# PWR_DC_IN.net
KiCad netlist of a schematic drawn in Altium Designer
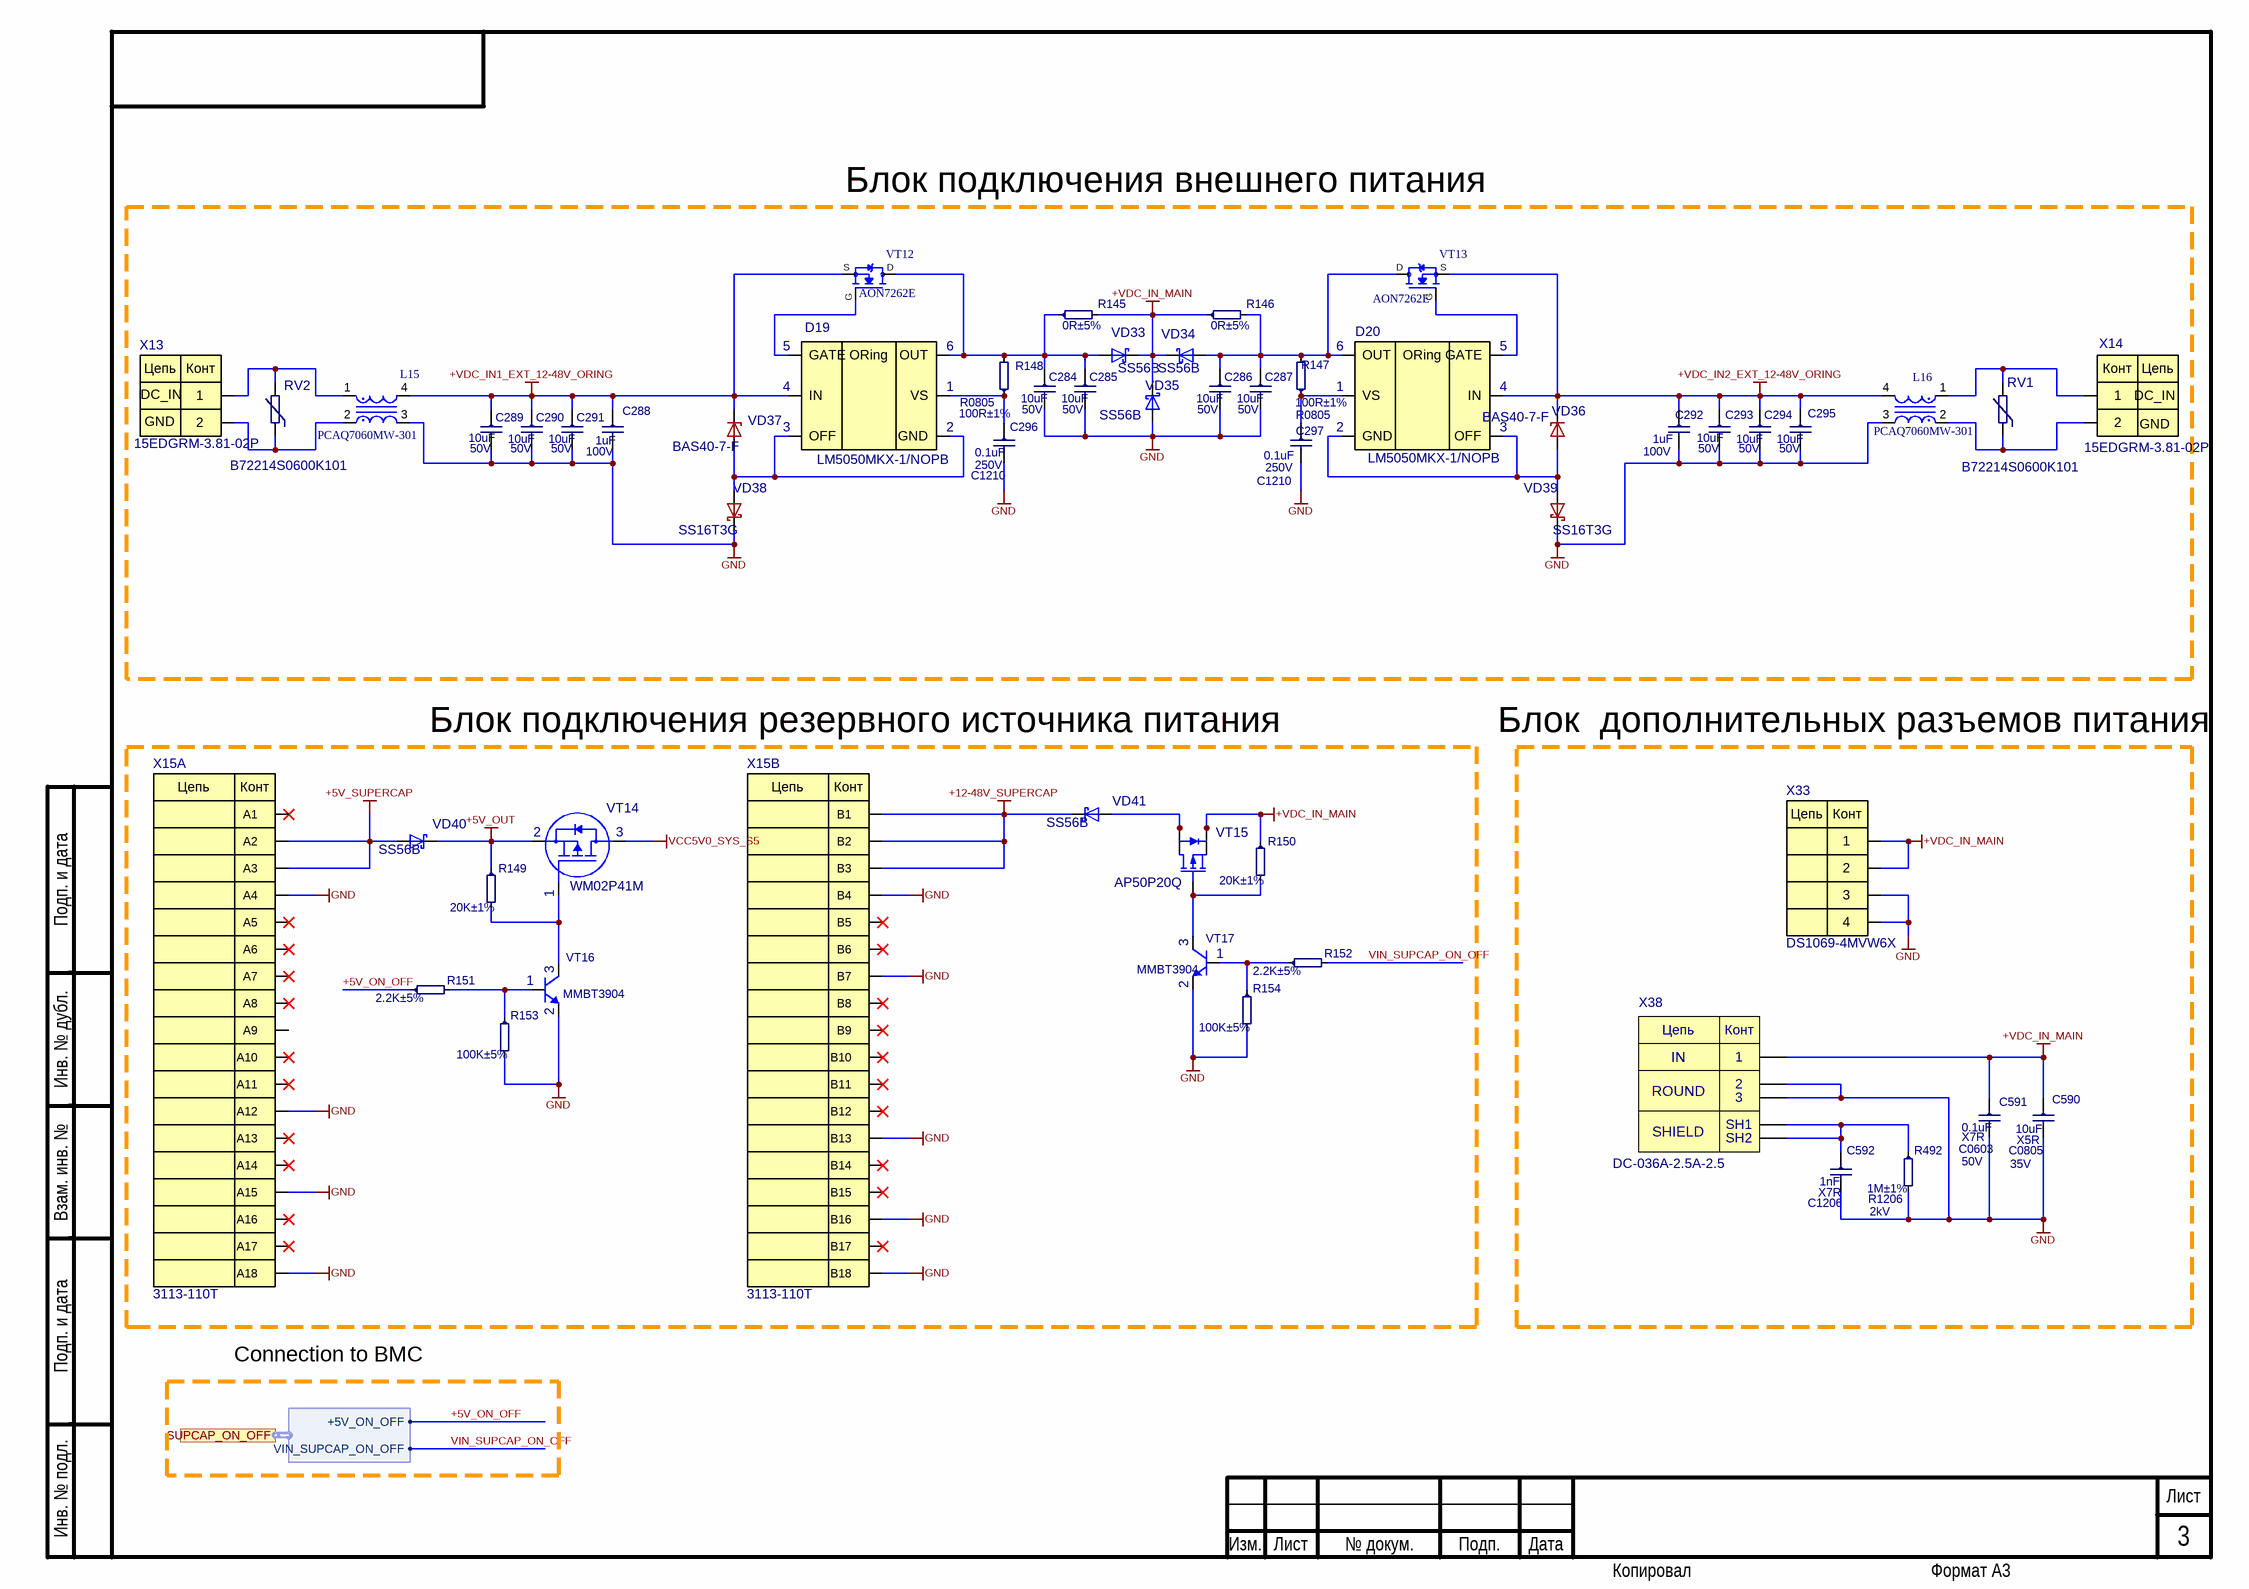
[diagram p0: PWR_DC_IN.SchDoc]

(export (version "E")
  (design (tool "Eeschema 10.0.6"))
  (components
    (comp (ref "C284")
      (value "10uF")
      (footprint "C1206")
      (fields
        (field (name "VOLTAGE") "50V")
        (field (name "PART NUMBER") "1206-X5R-50V-010uF±10%")
        (field (name "TOLERANCE") "10%")
        (field (name "MANUFACTURER") "Yageo")
      )
      (libsource (lib "ATB") (part "C"))
    )
    (comp (ref "C285")
      (value "10uF")
      (footprint "C1206")
      (fields
        (field (name "VOLTAGE") "50V")
        (field (name "PART NUMBER") "1206-X5R-50V-010uF±10%")
        (field (name "TOLERANCE") "10%")
        (field (name "MANUFACTURER") "Yageo")
      )
      (libsource (lib "ATB") (part "C"))
    )
    (comp (ref "C286")
      (value "10uF")
      (footprint "C1206")
      (fields
        (field (name "VOLTAGE") "50V")
        (field (name "PART NUMBER") "1206-X5R-50V-010uF±10%")
        (field (name "TOLERANCE") "10%")
        (field (name "MANUFACTURER") "Yageo")
      )
      (libsource (lib "ATB") (part "C"))
    )
    (comp (ref "C287")
      (value "10uF")
      (footprint "C1206")
      (fields
        (field (name "VOLTAGE") "50V")
        (field (name "PART NUMBER") "1206-X5R-50V-010uF±10%")
        (field (name "TOLERANCE") "10%")
        (field (name "MANUFACTURER") "Yageo")
      )
      (libsource (lib "ATB") (part "C"))
    )
    (comp (ref "C288")
      (value "1uF")
      (footprint "C1206")
      (fields
        (field (name "VOLTAGE") "100V")
        (field (name "PART NUMBER") "1206-X7R-100V-1uF±10%")
        (field (name "TOLERANCE") "10%")
        (field (name "MANUFACTURER") "CCTC")
      )
      (libsource (lib "ATB") (part "C"))
    )
    (comp (ref "C289")
      (value "10uF")
      (footprint "C1206")
      (fields
        (field (name "VOLTAGE") "50V")
        (field (name "PART NUMBER") "1206-X5R-50V-010uF±10%")
        (field (name "TOLERANCE") "10%")
        (field (name "MANUFACTURER") "Yageo")
      )
      (libsource (lib "ATB") (part "C"))
    )
    (comp (ref "C290")
      (value "10uF")
      (footprint "C1206")
      (fields
        (field (name "VOLTAGE") "50V")
        (field (name "PART NUMBER") "1206-X5R-50V-010uF±10%")
        (field (name "TOLERANCE") "10%")
        (field (name "MANUFACTURER") "Yageo")
      )
      (libsource (lib "ATB") (part "C"))
    )
    (comp (ref "C291")
      (value "10uF")
      (footprint "C1206")
      (fields
        (field (name "VOLTAGE") "50V")
        (field (name "PART NUMBER") "1206-X5R-50V-010uF±10%")
        (field (name "TOLERANCE") "10%")
        (field (name "MANUFACTURER") "Yageo")
      )
      (libsource (lib "ATB") (part "C"))
    )
    (comp (ref "C292")
      (value "1uF")
      (footprint "C1206")
      (fields
        (field (name "VOLTAGE") "100V")
        (field (name "PART NUMBER") "1206-X7R-100V-1uF±10%")
        (field (name "TOLERANCE") "10%")
        (field (name "MANUFACTURER") "CCTC")
      )
      (libsource (lib "ATB") (part "C"))
    )
    (comp (ref "C293")
      (value "10uF")
      (footprint "C1206")
      (fields
        (field (name "VOLTAGE") "50V")
        (field (name "PART NUMBER") "1206-X5R-50V-010uF±10%")
        (field (name "TOLERANCE") "10%")
        (field (name "MANUFACTURER") "Yageo")
      )
      (libsource (lib "ATB") (part "C"))
    )
    (comp (ref "C294")
      (value "10uF")
      (footprint "C1206")
      (fields
        (field (name "VOLTAGE") "50V")
        (field (name "PART NUMBER") "1206-X5R-50V-010uF±10%")
        (field (name "TOLERANCE") "10%")
        (field (name "MANUFACTURER") "Yageo")
      )
      (libsource (lib "ATB") (part "C"))
    )
    (comp (ref "C295")
      (value "10uF")
      (footprint "C1206")
      (fields
        (field (name "VOLTAGE") "50V")
        (field (name "PART NUMBER") "1206-X5R-50V-010uF±10%")
        (field (name "TOLERANCE") "10%")
        (field (name "MANUFACTURER") "Yageo")
      )
      (libsource (lib "ATB") (part "C"))
    )
    (comp (ref "C296")
      (value "0.1uF")
      (footprint "C1210")
      (fields
        (field (name "VOLTAGE") "250V")
        (field (name "CASE") "C1210")
        (field (name "PART NUMBER") "1210-X7R-250V-0.1uF±10%")
        (field (name "TOLERANCE") "10%")
        (field (name "MANUFACTURER") "Yageo")
      )
      (libsource (lib "ATB") (part "C"))
    )
    (comp (ref "C297")
      (value "0.1uF")
      (footprint "C1210")
      (fields
        (field (name "VOLTAGE") "250V")
        (field (name "CASE") "C1210")
        (field (name "PART NUMBER") "1210-X7R-250V-0.1uF±10%")
        (field (name "TOLERANCE") "10%")
        (field (name "MANUFACTURER") "Yageo")
      )
      (libsource (lib "ATB") (part "C"))
    )
    (comp (ref "C590")
      (value "10uF")
      (footprint "C0805")
      (fields
        (field (name "DIELECTRIC") "X5R")
        (field (name "VOLTAGE") "35V")
        (field (name "CASE") "C0805")
        (field (name "PART NUMBER") "0805-X5R-35V-10uF±10%")
        (field (name "TOLERANCE") "10%")
        (field (name "MANUFACTURER") "TDK Corporation")
      )
      (libsource (lib "ATB") (part "C"))
    )
    (comp (ref "C591")
      (value "0.1uF")
      (footprint "C0603")
      (fields
        (field (name "DIELECTRIC") "X7R")
        (field (name "VOLTAGE") "50V")
        (field (name "CASE") "C0603")
        (field (name "PART NUMBER") "0603-X7R-50V-0.1uF±10%")
        (field (name "TOLERANCE") "10%")
        (field (name "MANUFACTURER") "Yageo")
      )
      (libsource (lib "ATB") (part "C"))
    )
    (comp (ref "C592")
      (value "1nF")
      (footprint "C1206")
      (description "Ceramic Capacitor 1206 1nF ±10% 2kV X7R")
      (fields
        (field (name "DIELECTRIC") "X7R")
        (field (name "VOLTAGE") "2kV")
        (field (name "CASE") "C1206")
        (field (name "PART NUMBER") "1206-X7R-2K-1000pF±10%")
        (field (name "TOLERANCE") "10%")
      )
      (libsource (lib "ATB") (part "C"))
    )
    (comp (ref "D19")
      (value "LM5050MKX-1/NOPB")
      (footprint "LM5050MKX-1/NOPB")
      (description "High-Side OR-ing FET Controller")
      (fields (field (name "MANUFACTURER") "TI"))
      (libsource (lib "LIB_RK") (part "LM5050MKX-1/NOPB"))
    )
    (comp (ref "D20")
      (value "LM5050MKX-1/NOPB")
      (footprint "LM5050MKX-1/NOPB")
      (description "High-Side OR-ing FET Controller")
      (fields (field (name "MANUFACTURER") "TI"))
      (libsource (lib "") (part "LM5050MKX-1/NOPB_1"))
    )
    (comp (ref "L15")
      (value "PCAQ7060MW-301")
      (footprint "PCAQ7060MW-301")
      (description "300Ω@100MHz 10mΩ 2 SMD,7x6x3.8mm")
      (fields (field (name "MF") "Panasonic Electronic") (field (name "MP") "EEH-ZA1V151P"))
      (libsource (lib "") (part "PCAQ7060MW-301_1"))
    )
    (comp (ref "L16")
      (value "PCAQ7060MW-301")
      (footprint "PCAQ7060MW-301")
      (description "300Ω@100MHz 10mΩ 2 SMD,7x6x3.8mm")
      (fields (field (name "MF") "Panasonic Electronic") (field (name "MP") "EEH-ZA1V151P"))
      (libsource (lib "LIB_RK") (part "PCAQ7060MW-301"))
    )
    (comp (ref "R145")
      (value "0R±5%")
      (footprint "R2010")
      (description "Chip Resistor 2010 0Ω ±5% 200V ±200ppm/℃ Thick Film")
      (fields (field (name "PART NUMBER") "2010-0.75W-0R-200ppm±5%") (field (name "TOLERANCE") "5%"))
      (libsource (lib "ATB") (part "R"))
    )
    (comp (ref "R146")
      (value "0R±5%")
      (footprint "R2010")
      (description "Chip Resistor 2010 0Ω ±5% 200V ±200ppm/℃ Thick Film")
      (fields (field (name "PART NUMBER") "2010-0.75W-0R-200ppm±5%") (field (name "TOLERANCE") "5%"))
      (libsource (lib "ATB") (part "R"))
    )
    (comp (ref "R147")
      (value "100R±1%")
      (footprint "R0805")
      (fields
        (field (name "CASE") "R0805")
        (field (name "PART NUMBER") "0805-0.125W-100R-100ppm±1%")
        (field (name "TOLERANCE") "1%")
        (field (name "MANUFACTURER") "Yageo")
      )
      (libsource (lib "ATB") (part "R"))
    )
    (comp (ref "R148")
      (value "100R±1%")
      (footprint "R0805")
      (fields
        (field (name "CASE") "R0805")
        (field (name "PART NUMBER") "0805-0.125W-100R-100ppm±1%")
        (field (name "TOLERANCE") "1%")
        (field (name "MANUFACTURER") "Yageo")
      )
      (libsource (lib "ATB") (part "R"))
    )
    (comp (ref "R149")
      (value "20K±1%")
      (footprint "R0402")
      (description "Chip Resistor 0402 20kΩ ±1% 50V ±100ppm/℃ Thick Film")
      (fields (field (name "PART NUMBER") "0402-0.0625W-20K-100ppm±1%") (field (name "TOLERANCE") "1%"))
      (libsource (lib "ATB") (part "R"))
    )
    (comp (ref "R150")
      (value "20K±1%")
      (footprint "R0402")
      (description "Chip Resistor 0402 20kΩ ±1% 50V ±100ppm/℃ Thick Film")
      (fields (field (name "PART NUMBER") "0402-0.0625W-20K-100ppm±1%") (field (name "TOLERANCE") "1%"))
      (libsource (lib "ATB") (part "R"))
    )
    (comp (ref "R151")
      (value "2.2K±5%")
      (footprint "R0402")
      (fields
        (field (name "PART NUMBER") "0402-0.0625W-2.2K-100ppm±5%")
        (field (name "TOLERANCE") "5%")
        (field (name "MANUFACTURER") "Yageo")
      )
      (libsource (lib "ATB") (part "R"))
    )
    (comp (ref "R152")
      (value "2.2K±5%")
      (footprint "R0402")
      (fields
        (field (name "PART NUMBER") "0402-0.0625W-2.2K-100ppm±5%")
        (field (name "TOLERANCE") "5%")
        (field (name "MANUFACTURER") "Yageo")
      )
      (libsource (lib "ATB") (part "R"))
    )
    (comp (ref "R153")
      (value "100K±5%")
      (footprint "R0402")
      (fields
        (field (name "PART NUMBER") "0402-0.0625W-100K-100ppm±5%")
        (field (name "TOLERANCE") "5%")
        (field (name "MANUFACTURER") "Yageo")
      )
      (libsource (lib "ATB") (part "R"))
    )
    (comp (ref "R154")
      (value "100K±5%")
      (footprint "R0402")
      (fields
        (field (name "PART NUMBER") "0402-0.0625W-100K-100ppm±5%")
        (field (name "TOLERANCE") "5%")
        (field (name "MANUFACTURER") "Yageo")
      )
      (libsource (lib "ATB") (part "R"))
    )
    (comp (ref "R492")
      (value "1M±1%")
      (footprint "R1206")
      (description "Chip Resistor 1206 1MΩ ±1% 200V ±100ppm/℃ Thick Film")
      (fields
        (field (name "CASE") "R1206")
        (field (name "PART NUMBER") "1206-0.25W-1M-100ppm±1%")
        (field (name "TOLERANCE") "1%")
      )
      (libsource (lib "ATB") (part "R"))
    )
    (comp (ref "RV1")
      (value "B72214S0600K101")
      (footprint "Var_dia15.5")
      (description "Varistor")
      (fields (field (name "VOLTAGE") "320V") (field (name "MANUFACTURER") "Epcos"))
      (libsource (lib "ATB") (part "RV"))
    )
    (comp (ref "RV2")
      (value "B72214S0600K101")
      (footprint "Var_dia15.5")
      (description "Varistor")
      (fields (field (name "VOLTAGE") "320V") (field (name "MANUFACTURER") "Epcos"))
      (libsource (lib "ATB") (part "RV"))
    )
    (comp (ref "VD33")
      (value "SS56B")
      (footprint "DO-214AA")
      (description "Schottky Rectifier")
      (fields (field (name "MANUFACTURER") "Yangjie (YJ)"))
      (libsource (lib "ATB") (part "Shotki"))
    )
    (comp (ref "VD34")
      (value "SS56B")
      (footprint "DO-214AA")
      (description "Schottky Rectifier")
      (fields (field (name "MANUFACTURER") "Yangjie (YJ)"))
      (libsource (lib "ATB") (part "Shotki"))
    )
    (comp (ref "VD35")
      (value "SS56B")
      (footprint "DO-214AA")
      (description "Schottky Rectifier")
      (fields (field (name "MANUFACTURER") "Yangjie (YJ)"))
      (libsource (lib "ATB") (part "Shotki"))
    )
    (comp (ref "VD36")
      (value "BAS40-7-F")
      (footprint "SOT23")
      (description "600mA 1 Independent 40V 1V@40mA 200mA SOT-23 Single Diodes RoHS")
      (fields (field (name "MANUFACTURER") "Diodes Incorporated"))
      (libsource (lib "ATB") (part "LM4040"))
    )
    (comp (ref "VD37")
      (value "BAS40-7-F")
      (footprint "SOT23")
      (description "600mA 1 Independent 40V 1V@40mA 200mA SOT-23 Single Diodes RoHS")
      (fields (field (name "MANUFACTURER") "Diodes Incorporated"))
      (libsource (lib "ATB") (part "LM4040"))
    )
    (comp (ref "VD38")
      (value "SS16T3G")
      (footprint "DO-214AC")
      (description "Schottky Power Rectifier")
      (fields (field (name "MANUFACTURER") "ON Semiconductor"))
      (libsource (lib "") (part "Shotki_1"))
    )
    (comp (ref "VD39")
      (value "SS16T3G")
      (footprint "DO-214AC")
      (description "Schottky Power Rectifier")
      (fields (field (name "MANUFACTURER") "ON Semiconductor"))
      (libsource (lib "") (part "Shotki_1"))
    )
    (comp (ref "VD40")
      (value "SS56B")
      (footprint "DO-214AA")
      (description "Schottky Rectifier")
      (fields (field (name "MANUFACTURER") "Yangjie (YJ)"))
      (libsource (lib "ATB") (part "Shotki"))
    )
    (comp (ref "VD41")
      (value "SS56B")
      (footprint "DO-214AA")
      (description "Schottky Rectifier")
      (fields (field (name "MANUFACTURER") "Yangjie (YJ)"))
      (libsource (lib "ATB") (part "Shotki"))
    )
    (comp (ref "VT12")
      (value "AON7262E")
      (footprint "AON7262E")
      (description "60V 6.2mΩ@10V,20A 2.2V@250uA N Channel DFN-8(3.3x3.3) MOSFET")
      (fields (field (name "MANUFACTURER") "Alpha & Omega"))
      (libsource (lib "LIB_RK") (part "AON7262E"))
    )
    (comp (ref "VT13")
      (value "AON7262E")
      (footprint "AON7262E")
      (description "60V 6.2mΩ@10V,20A 2.2V@250uA N Channel DFN-8(3.3x3.3) MOSFET")
      (fields (field (name "MANUFACTURER") "Alpha & Omega"))
      (libsource (lib "LIB_RK") (part "AON7262E"))
    )
    (comp (ref "VT14")
      (value "WM02P41M")
      (footprint "SOT23")
      (description "Small signal mosfet")
      (fields (field (name "VOLTAGE") "-20V") (field (name "MANUFACTURER") "Wayon"))
      (libsource (lib "ATB") (part "WM02P41M"))
    )
    (comp (ref "VT15")
      (value "AP50P20Q")
      (footprint "AP50P20Q")
      (description "20V 50A 40W 6.6mΩ@4.5V,15A 650mV@250uA P Channel WDFN-8(3x3) MOSFETs")
      (fields (field (name "MANUFACTURER") "ALLPOWER"))
      (libsource (lib "LIB_RK") (part "AP50P20Q"))
    )
    (comp (ref "VT16")
      (value "MMBT3904")
      (footprint "SOT23")
      (description "NPN transistor")
      (fields (field (name "VOLTAGE") "40V") (field (name "MANUFACTURER") "Diotec Semiconductor"))
      (libsource (lib "ATB") (part "BC846BLT1G"))
    )
    (comp (ref "VT17")
      (value "MMBT3904")
      (footprint "SOT23")
      (description "NPN transistor")
      (fields (field (name "VOLTAGE") "40V") (field (name "MANUFACTURER") "Diotec Semiconductor"))
      (libsource (lib "ATB") (part "BC846BLT1G"))
    )
    (comp (ref "X13")
      (value "15EDGRM-3.81-02P")
      (footprint "15EDGRM-3.81-02P")
      (description "Разъемный клеммный блок на плату, 2 контакта. Серия 15EDGRM-3.81")
      (fields (field (name "MANUFACTURER") "DEGSON"))
      (libsource (lib "LIB_RK") (part "15EDGRM-3.81-02P"))
    )
    (comp (ref "X14")
      (value "15EDGRM-3.81-02P")
      (footprint "15EDGRM-3.81-02P")
      (description "Разъемный клеммный блок на плату, 2 контакта. Серия 15EDGRM-3.81")
      (fields (field (name "MANUFACTURER") "DEGSON"))
      (libsource (lib "") (part "15EDGRM-3.81-02P_1"))
    )
    (comp (ref "X15")
      (value "3113-110T")
      (footprint "3113-110T")
      (description "PCI Connector, Vertical, Surface Mount, x1, 36 Positions, 1.00mm (0.039in) Pitch")
      (fields (field (name "MANUFACTURER") "UMAX"))
      (libsource (lib "LIB_RK") (part "3113-110T"))
    )
    (comp (ref "X33")
      (value "DS1069-4MVW6X")
      (footprint "DS1069-4MVW6X")
      (description "1 XH 4P -25℃~+85℃ 2.5mm 3A 250V 1x4P Through Hole,P=2.5mm Headers, Male Pins RoHS")
      (fields (field (name "MANUFACTURER") "CONNFLY"))
      (libsource (lib "LIB_RK") (part "DS1069-4MVW6X"))
    )
    (comp (ref "X38")
      (value "DC-036A-2.5A-2.5")
      (footprint "DC-036A-2.5A-2.5")
      (description "DC Power Connector Bend-in, -20℃~+70℃, 2.5mm 6mm, 2.5A 24V")
      (fields (field (name "MANUFACTURER") "XKB Connection"))
      (libsource (lib "ATB") (part "DC-036A-2.5A-2.5"))
    )
  )
  (nets
    (net (code "2") (name "+5V_OUT") (class "Default")
      (node (ref "R149") (pin "1") (pinfunction "1_1") (pintype "passive"))
      (node (ref "VD40") (pin "1") (pinfunction "K_1") (pintype "passive"))
      (node (ref "VT14") (pin "2") (pinfunction "2_2") (pintype "passive"))
    )
    (net (code "3") (name "+5V_SUPERCAP") (class "Default")
      (node (ref "VD40") (pin "2") (pinfunction "A_2") (pintype "passive"))
      (node (ref "X15") (pin "A2") (pinfunction "A2_A2") (pintype "passive"))
      (node (ref "X15") (pin "A3") (pinfunction "A3_A3") (pintype "passive"))
    )
    (net (code "4") (name "+12-48V_SUPERCAP") (class "Default")
      (node (ref "VD41") (pin "1") (pinfunction "K_1") (pintype "passive"))
      (node (ref "X15") (pin "B1") (pinfunction "B1_B1") (pintype "passive"))
      (node (ref "X15") (pin "B2") (pinfunction "B2_B2") (pintype "passive"))
      (node (ref "X15") (pin "B3") (pinfunction "B3_B3") (pintype "passive"))
    )
    (net (code "5") (name "+VDC_IN1_EXT_12-48V_ORING") (class "Default")
      (node (ref "C288") (pin "1") (pinfunction "1_1") (pintype "passive"))
      (node (ref "C289") (pin "1") (pinfunction "1_1") (pintype "passive"))
      (node (ref "C290") (pin "1") (pinfunction "1_1") (pintype "passive"))
      (node (ref "C291") (pin "1") (pinfunction "1_1") (pintype "passive"))
      (node (ref "D19") (pin "4") (pinfunction "IN_4") (pintype "passive"))
      (node (ref "L15") (pin "4") (pinfunction "4_4") (pintype "passive"))
      (node (ref "VD37") (pin "1") (pinfunction "C_1") (pintype "passive"))
      (node (ref "VT12") (pin "S") (pinfunction "S_S") (pintype "passive"))
    )
    (net (code "6") (name "+VDC_IN2_EXT_12-48V_ORING") (class "Default")
      (node (ref "C292") (pin "1") (pinfunction "1_1") (pintype "passive"))
      (node (ref "C293") (pin "1") (pinfunction "1_1") (pintype "passive"))
      (node (ref "C294") (pin "1") (pinfunction "1_1") (pintype "passive"))
      (node (ref "C295") (pin "1") (pinfunction "1_1") (pintype "passive"))
      (node (ref "D20") (pin "4") (pinfunction "IN_4") (pintype "passive"))
      (node (ref "L16") (pin "4") (pinfunction "4_4") (pintype "passive"))
      (node (ref "VD36") (pin "1") (pinfunction "C_1") (pintype "passive"))
      (node (ref "VT13") (pin "S") (pinfunction "S_S") (pintype "passive"))
    )
    (net (code "7") (name "+VDC_IN_MAIN") (class "Default")
      (node (ref "C590") (pin "1") (pinfunction "1_1") (pintype "passive"))
      (node (ref "C591") (pin "1") (pinfunction "1_1") (pintype "passive"))
      (node (ref "R145") (pin "2") (pinfunction "2_2") (pintype "passive"))
      (node (ref "R146") (pin "1") (pinfunction "1_1") (pintype "passive"))
      (node (ref "R150") (pin "1") (pinfunction "1_1") (pintype "passive"))
      (node (ref "VD33") (pin "1") (pinfunction "K_1") (pintype "passive"))
      (node (ref "VD34") (pin "1") (pinfunction "K_1") (pintype "passive"))
      (node (ref "VD35") (pin "1") (pinfunction "K_1") (pintype "passive"))
      (node (ref "VT15") (pin "1") (pinfunction "1_1") (pintype "passive"))
      (node (ref "VT15") (pin "2") (pinfunction "2_2") (pintype "passive"))
      (node (ref "VT15") (pin "3") (pinfunction "3_3") (pintype "passive"))
      (node (ref "X33") (pin "1") (pinfunction "1_1") (pintype "passive"))
      (node (ref "X33") (pin "2") (pinfunction "2_2") (pintype "passive"))
      (node (ref "X38") (pin "1") (pinfunction "IN_1") (pintype "passive"))
    )
    (net (code "8") (name "/+5V_ON_OFF") (class "Default")
      (node (ref "R151") (pin "1") (pinfunction "1_1") (pintype "passive"))
    )
    (net (code "9") (name "/VIN_SUPCAP_ON_OFF") (class "Default")
      (node (ref "R152") (pin "2") (pinfunction "2_2") (pintype "passive"))
    )
    (net (code "11") (name "GND") (class "Default")
      (node (ref "C284") (pin "2") (pinfunction "2_2") (pintype "passive"))
      (node (ref "C285") (pin "2") (pinfunction "2_2") (pintype "passive"))
      (node (ref "C286") (pin "2") (pinfunction "2_2") (pintype "passive"))
      (node (ref "C287") (pin "2") (pinfunction "2_2") (pintype "passive"))
      (node (ref "C288") (pin "2") (pinfunction "2_2") (pintype "passive"))
      (node (ref "C289") (pin "2") (pinfunction "2_2") (pintype "passive"))
      (node (ref "C290") (pin "2") (pinfunction "2_2") (pintype "passive"))
      (node (ref "C291") (pin "2") (pinfunction "2_2") (pintype "passive"))
      (node (ref "C292") (pin "2") (pinfunction "2_2") (pintype "passive"))
      (node (ref "C293") (pin "2") (pinfunction "2_2") (pintype "passive"))
      (node (ref "C294") (pin "2") (pinfunction "2_2") (pintype "passive"))
      (node (ref "C295") (pin "2") (pinfunction "2_2") (pintype "passive"))
      (node (ref "C296") (pin "2") (pinfunction "2_2") (pintype "passive"))
      (node (ref "C297") (pin "2") (pinfunction "2_2") (pintype "passive"))
      (node (ref "C590") (pin "2") (pinfunction "2_2") (pintype "passive"))
      (node (ref "C591") (pin "2") (pinfunction "2_2") (pintype "passive"))
      (node (ref "C592") (pin "2") (pinfunction "2_2") (pintype "passive"))
      (node (ref "L15") (pin "3") (pinfunction "3_3") (pintype "passive"))
      (node (ref "L16") (pin "3") (pinfunction "3_3") (pintype "passive"))
      (node (ref "R153") (pin "2") (pinfunction "2_2") (pintype "passive"))
      (node (ref "R154") (pin "2") (pinfunction "2_2") (pintype "passive"))
      (node (ref "R492") (pin "2") (pinfunction "2_2") (pintype "passive"))
      (node (ref "VD35") (pin "2") (pinfunction "A_2") (pintype "passive"))
      (node (ref "VD38") (pin "1") (pinfunction "C_1") (pintype "passive"))
      (node (ref "VD39") (pin "1") (pinfunction "C_1") (pintype "passive"))
      (node (ref "VT16") (pin "2") (pinfunction "E_2") (pintype "passive"))
      (node (ref "VT17") (pin "2") (pinfunction "E_2") (pintype "passive"))
      (node (ref "X15") (pin "A12") (pinfunction "A12_A12") (pintype "passive"))
      (node (ref "X15") (pin "A15") (pinfunction "A15_A15") (pintype "passive"))
      (node (ref "X15") (pin "A18") (pinfunction "A18_A18") (pintype "passive"))
      (node (ref "X15") (pin "A4") (pinfunction "A4_A4") (pintype "passive"))
      (node (ref "X15") (pin "B13") (pinfunction "B13_B13") (pintype "passive"))
      (node (ref "X15") (pin "B16") (pinfunction "B16_B16") (pintype "passive"))
      (node (ref "X15") (pin "B18") (pinfunction "B18_B18") (pintype "passive"))
      (node (ref "X15") (pin "B4") (pinfunction "B4_B4") (pintype "passive"))
      (node (ref "X15") (pin "B7") (pinfunction "B7_B7") (pintype "passive"))
      (node (ref "X33") (pin "3") (pinfunction "3_3") (pintype "passive"))
      (node (ref "X33") (pin "4") (pinfunction "4_4") (pintype "passive"))
      (node (ref "X38") (pin "2") (pinfunction "ROUND_2") (pintype "passive"))
      (node (ref "X38") (pin "3") (pinfunction "ROUND_3") (pintype "passive"))
    )
    (net (code "12") (name "Net-(C592-Pad1)") (class "Default")
      (node (ref "C592") (pin "1") (pinfunction "1_1") (pintype "passive"))
      (node (ref "R492") (pin "1") (pinfunction "1_1") (pintype "passive"))
      (node (ref "X38") (pin "SH1") (pinfunction "SH1_SH1") (pintype "passive"))
      (node (ref "X38") (pin "SH2") (pinfunction "SH2_SH2") (pintype "passive"))
    )
    (net (code "13") (name "Net-(D19-GATE)") (class "Default")
      (node (ref "D19") (pin "5") (pinfunction "GATE_5") (pintype "passive"))
      (node (ref "VT12") (pin "G") (pinfunction "G_G") (pintype "passive"))
    )
    (net (code "14") (name "Net-(D19-GND)") (class "Default")
      (node (ref "D19") (pin "2") (pinfunction "GND_2") (pintype "passive"))
      (node (ref "D19") (pin "3") (pinfunction "OFF_3") (pintype "passive"))
      (node (ref "VD37") (pin "2") (pinfunction "A_2") (pintype "passive"))
      (node (ref "VD38") (pin "2") (pinfunction "A_2") (pintype "passive"))
    )
    (net (code "15") (name "Net-(D19-OUT)") (class "Default")
      (node (ref "C284") (pin "1") (pinfunction "1_1") (pintype "passive"))
      (node (ref "C285") (pin "1") (pinfunction "1_1") (pintype "passive"))
      (node (ref "D19") (pin "6") (pinfunction "OUT_6") (pintype "passive"))
      (node (ref "R145") (pin "1") (pinfunction "1_1") (pintype "passive"))
      (node (ref "R148") (pin "2") (pinfunction "2_2") (pintype "passive"))
      (node (ref "VD33") (pin "2") (pinfunction "A_2") (pintype "passive"))
      (node (ref "VT12") (pin "D") (pinfunction "D_D") (pintype "passive"))
    )
    (net (code "16") (name "Net-(D19-VS)") (class "Default")
      (node (ref "C296") (pin "1") (pinfunction "1_1") (pintype "passive"))
      (node (ref "D19") (pin "1") (pinfunction "VS_1") (pintype "passive"))
      (node (ref "R148") (pin "1") (pinfunction "1_1") (pintype "passive"))
    )
    (net (code "17") (name "Net-(D20-GATE)") (class "Default")
      (node (ref "D20") (pin "5") (pinfunction "GATE_5") (pintype "passive"))
      (node (ref "VT13") (pin "G") (pinfunction "G_G") (pintype "passive"))
    )
    (net (code "18") (name "Net-(D20-GND)") (class "Default")
      (node (ref "D20") (pin "2") (pinfunction "GND_2") (pintype "passive"))
      (node (ref "D20") (pin "3") (pinfunction "OFF_3") (pintype "passive"))
      (node (ref "VD36") (pin "2") (pinfunction "A_2") (pintype "passive"))
      (node (ref "VD39") (pin "2") (pinfunction "A_2") (pintype "passive"))
    )
    (net (code "19") (name "Net-(D20-OUT)") (class "Default")
      (node (ref "C286") (pin "1") (pinfunction "1_1") (pintype "passive"))
      (node (ref "C287") (pin "1") (pinfunction "1_1") (pintype "passive"))
      (node (ref "D20") (pin "6") (pinfunction "OUT_6") (pintype "passive"))
      (node (ref "R146") (pin "2") (pinfunction "2_2") (pintype "passive"))
      (node (ref "R147") (pin "2") (pinfunction "2_2") (pintype "passive"))
      (node (ref "VD34") (pin "2") (pinfunction "A_2") (pintype "passive"))
      (node (ref "VT13") (pin "D") (pinfunction "D_D") (pintype "passive"))
    )
    (net (code "20") (name "Net-(D20-VS)") (class "Default")
      (node (ref "C297") (pin "1") (pinfunction "1_1") (pintype "passive"))
      (node (ref "D20") (pin "1") (pinfunction "VS_1") (pintype "passive"))
      (node (ref "R147") (pin "1") (pinfunction "1_1") (pintype "passive"))
    )
    (net (code "21") (name "Net-(L15-Pad1)") (class "Default")
      (node (ref "L15") (pin "1") (pinfunction "1_1") (pintype "passive"))
      (node (ref "RV2") (pin "2") (pinfunction "2_2") (pintype "passive"))
      (node (ref "X13") (pin "1") (pinfunction "1_1") (pintype "passive"))
    )
    (net (code "22") (name "Net-(L15-Pad2)") (class "Default")
      (node (ref "L15") (pin "2") (pinfunction "2_2") (pintype "passive"))
      (node (ref "RV2") (pin "1") (pinfunction "1_1") (pintype "passive"))
      (node (ref "X13") (pin "2") (pinfunction "2_2") (pintype "passive"))
    )
    (net (code "23") (name "Net-(L16-Pad1)") (class "Default")
      (node (ref "L16") (pin "1") (pinfunction "1_1") (pintype "passive"))
      (node (ref "RV1") (pin "2") (pinfunction "2_2") (pintype "passive"))
      (node (ref "X14") (pin "1") (pinfunction "1_1") (pintype "passive"))
    )
    (net (code "24") (name "Net-(L16-Pad2)") (class "Default")
      (node (ref "L16") (pin "2") (pinfunction "2_2") (pintype "passive"))
      (node (ref "RV1") (pin "1") (pinfunction "1_1") (pintype "passive"))
      (node (ref "X14") (pin "2") (pinfunction "2_2") (pintype "passive"))
    )
    (net (code "25") (name "Net-(VD41-A)") (class "Default")
      (node (ref "VD41") (pin "2") (pinfunction "A_2") (pintype "passive"))
      (node (ref "VT15") (pin "5") (pinfunction "5_5") (pintype "passive"))
      (node (ref "VT15") (pin "6") (pinfunction "6_6") (pintype "passive"))
      (node (ref "VT15") (pin "7") (pinfunction "7_7") (pintype "passive"))
      (node (ref "VT15") (pin "8") (pinfunction "8_8") (pintype "passive"))
    )
    (net (code "26") (name "Net-(VT16-B)") (class "Default")
      (node (ref "R151") (pin "2") (pinfunction "2_2") (pintype "passive"))
      (node (ref "R153") (pin "1") (pinfunction "1_1") (pintype "passive"))
      (node (ref "VT16") (pin "1") (pinfunction "B_1") (pintype "passive"))
    )
    (net (code "27") (name "Net-(VT16-C)") (class "Default")
      (node (ref "R149") (pin "2") (pinfunction "2_2") (pintype "passive"))
      (node (ref "VT14") (pin "1") (pinfunction "1_1") (pintype "passive"))
      (node (ref "VT16") (pin "3") (pinfunction "C_3") (pintype "passive"))
    )
    (net (code "28") (name "Net-(VT17-B)") (class "Default")
      (node (ref "R152") (pin "1") (pinfunction "1_1") (pintype "passive"))
      (node (ref "R154") (pin "1") (pinfunction "1_1") (pintype "passive"))
      (node (ref "VT17") (pin "1") (pinfunction "B_1") (pintype "passive"))
    )
    (net (code "29") (name "Net-(VT17-C)") (class "Default")
      (node (ref "R150") (pin "2") (pinfunction "2_2") (pintype "passive"))
      (node (ref "VT15") (pin "4") (pinfunction "4_4") (pintype "passive"))
      (node (ref "VT17") (pin "3") (pinfunction "C_3") (pintype "passive"))
    )
    (net (code "30") (name "VCC5V0_SYS_S5") (class "Default")
      (node (ref "VT14") (pin "3") (pinfunction "3_3") (pintype "passive"))
    )
    (net (code "31") (name "unconnected-(X15-PadA1)") (class "Default")
      (node (ref "X15") (pin "A1") (pinfunction "A1_A1") (pintype "passive+no_connect"))
    )
    (net (code "32") (name "unconnected-(X15-PadA5)") (class "Default")
      (node (ref "X15") (pin "A5") (pinfunction "A5_A5") (pintype "passive+no_connect"))
    )
    (net (code "33") (name "unconnected-(X15-PadA6)") (class "Default")
      (node (ref "X15") (pin "A6") (pinfunction "A6_A6") (pintype "passive+no_connect"))
    )
    (net (code "34") (name "unconnected-(X15-PadA7)") (class "Default")
      (node (ref "X15") (pin "A7") (pinfunction "A7_A7") (pintype "passive+no_connect"))
    )
    (net (code "35") (name "unconnected-(X15-PadA8)") (class "Default")
      (node (ref "X15") (pin "A8") (pinfunction "A8_A8") (pintype "passive+no_connect"))
    )
    (net (code "36") (name "unconnected-(X15-PadA9)") (class "Default")
      (node (ref "X15") (pin "A9") (pinfunction "A9_A9") (pintype "passive"))
    )
    (net (code "37") (name "unconnected-(X15-PadA10)") (class "Default")
      (node (ref "X15") (pin "A10") (pinfunction "A10_A10") (pintype "passive+no_connect"))
    )
    (net (code "38") (name "unconnected-(X15-PadA11)") (class "Default")
      (node (ref "X15") (pin "A11") (pinfunction "A11_A11") (pintype "passive+no_connect"))
    )
    (net (code "39") (name "unconnected-(X15-PadA13)") (class "Default")
      (node (ref "X15") (pin "A13") (pinfunction "A13_A13") (pintype "passive+no_connect"))
    )
    (net (code "40") (name "unconnected-(X15-PadA14)") (class "Default")
      (node (ref "X15") (pin "A14") (pinfunction "A14_A14") (pintype "passive+no_connect"))
    )
    (net (code "41") (name "unconnected-(X15-PadA16)") (class "Default")
      (node (ref "X15") (pin "A16") (pinfunction "A16_A16") (pintype "passive+no_connect"))
    )
    (net (code "42") (name "unconnected-(X15-PadA17)") (class "Default")
      (node (ref "X15") (pin "A17") (pinfunction "A17_A17") (pintype "passive+no_connect"))
    )
    (net (code "43") (name "unconnected-(X15-PadB5)") (class "Default")
      (node (ref "X15") (pin "B5") (pinfunction "B5_B5") (pintype "passive+no_connect"))
    )
    (net (code "44") (name "unconnected-(X15-PadB6)") (class "Default")
      (node (ref "X15") (pin "B6") (pinfunction "B6_B6") (pintype "passive+no_connect"))
    )
    (net (code "45") (name "unconnected-(X15-PadB8)") (class "Default")
      (node (ref "X15") (pin "B8") (pinfunction "B8_B8") (pintype "passive+no_connect"))
    )
    (net (code "46") (name "unconnected-(X15-PadB9)") (class "Default")
      (node (ref "X15") (pin "B9") (pinfunction "B9_B9") (pintype "passive+no_connect"))
    )
    (net (code "47") (name "unconnected-(X15-PadB10)") (class "Default")
      (node (ref "X15") (pin "B10") (pinfunction "B10_B10") (pintype "passive+no_connect"))
    )
    (net (code "48") (name "unconnected-(X15-PadB11)") (class "Default")
      (node (ref "X15") (pin "B11") (pinfunction "B11_B11") (pintype "passive+no_connect"))
    )
    (net (code "49") (name "unconnected-(X15-PadB12)") (class "Default")
      (node (ref "X15") (pin "B12") (pinfunction "B12_B12") (pintype "passive+no_connect"))
    )
    (net (code "50") (name "unconnected-(X15-PadB14)") (class "Default")
      (node (ref "X15") (pin "B14") (pinfunction "B14_B14") (pintype "passive+no_connect"))
    )
    (net (code "51") (name "unconnected-(X15-PadB15)") (class "Default")
      (node (ref "X15") (pin "B15") (pinfunction "B15_B15") (pintype "passive+no_connect"))
    )
    (net (code "52") (name "unconnected-(X15-PadB17)") (class "Default")
      (node (ref "X15") (pin "B17") (pinfunction "B17_B17") (pintype "passive+no_connect"))
    )
  )
)
